# 5V_-_3_3V_regulator.net
KiCad netlist of a schematic drawn in Altium Designer
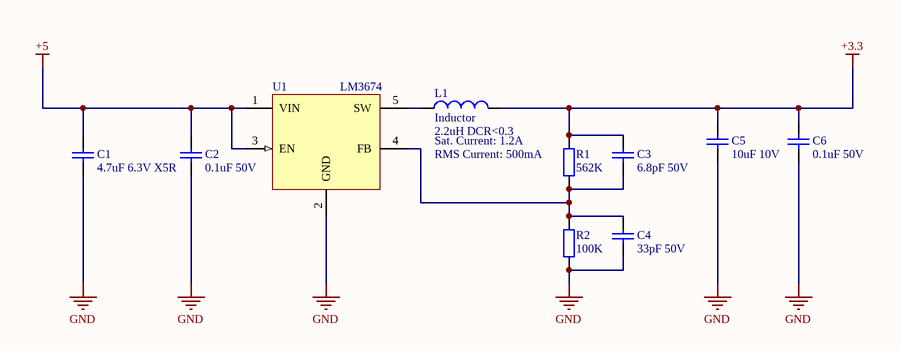
[diagram p0: 5V - 3.3V regulator.SchDoc]

(export (version "E")
  (design (tool "Eeschema 10.0.6"))
  (components
    (comp (ref "C1")
      (value "4.7uF 6.3V X5R")
      (description "Capacitor")
      (fields (field (name "Comment") "Cap"))
      (libsource (lib "Miscellaneous Devices") (part "Cap"))
    )
    (comp (ref "C2")
      (value "0.1uF 50V")
      (description "Capacitor")
      (fields (field (name "Comment") "Cap"))
      (libsource (lib "Miscellaneous Devices") (part "Cap"))
    )
    (comp (ref "C3")
      (value "6.8pF 50V")
      (description "Capacitor")
      (fields (field (name "Comment") "Cap"))
      (libsource (lib "Miscellaneous Devices") (part "Cap"))
    )
    (comp (ref "C4")
      (value "33pF 50V")
      (description "Capacitor")
      (fields (field (name "Comment") "Cap"))
      (libsource (lib "Miscellaneous Devices") (part "Cap"))
    )
    (comp (ref "C5")
      (value "10uF 10V")
      (description "Capacitor")
      (fields (field (name "Comment") "Cap"))
      (libsource (lib "Miscellaneous Devices") (part "Cap"))
    )
    (comp (ref "C6")
      (value "0.1uF 50V")
      (description "Capacitor")
      (fields (field (name "Comment") "Cap"))
      (libsource (lib "Miscellaneous Devices") (part "Cap"))
    )
    (comp (ref "L1")
      (value "Inductor")
      (footprint "B82422H1222K")
      (fields
        (field (name "ALTIUM_VALUE") "2.2uH DCR<0.3")
        (field (name "SAT. CURRENT") "1.2A")
        (field (name "RMS CURRENT") "500mA")
      )
      (libsource (lib "Miscellaneous Devices") (part "Inductor"))
    )
    (comp (ref "R1")
      (value "562K")
      (footprint "MC0603")
      (description "Resistor")
      (fields (field (name "Comment") "Res"))
      (libsource (lib "Miscellaneous Devices") (part "Res2"))
    )
    (comp (ref "R2")
      (value "100K")
      (footprint "MC0603")
      (description "Resistor")
      (fields (field (name "Comment") "Res"))
      (libsource (lib "Miscellaneous Devices") (part "Res2"))
    )
    (comp (ref "U1")
      (value "LM3674")
      (footprint "LM3674MF-ADJ")
      (description "5V STEP DOWN CONV, 600MA, POWERWISE")
      (libsource (lib "mcb") (part "LM3674"))
    )
  )
  (nets
    (net (code "1") (name "+3.3") (class "Default")
      (node (ref "C3") (pin "2") (pinfunction "2_2") (pintype "passive"))
      (node (ref "C5") (pin "2") (pinfunction "2_2") (pintype "passive"))
      (node (ref "C6") (pin "2") (pinfunction "2_2") (pintype "passive"))
      (node (ref "L1") (pin "2") (pinfunction "2_2") (pintype "passive"))
      (node (ref "R1") (pin "2") (pinfunction "2_2") (pintype "passive"))
    )
    (net (code "2") (name "+5") (class "Default")
      (node (ref "C1") (pin "2") (pinfunction "2_2") (pintype "passive"))
      (node (ref "C2") (pin "2") (pinfunction "2_2") (pintype "passive"))
      (node (ref "U1") (pin "1") (pinfunction "VIN_1") (pintype "power_in"))
      (node (ref "U1") (pin "3") (pinfunction "EN_3") (pintype "input"))
    )
    (net (code "3") (name "GND") (class "Default")
      (node (ref "C1") (pin "1") (pinfunction "1_1") (pintype "passive"))
      (node (ref "C2") (pin "1") (pinfunction "1_1") (pintype "passive"))
      (node (ref "C4") (pin "1") (pinfunction "1_1") (pintype "passive"))
      (node (ref "C5") (pin "1") (pinfunction "1_1") (pintype "passive"))
      (node (ref "C6") (pin "1") (pinfunction "1_1") (pintype "passive"))
      (node (ref "R2") (pin "1") (pinfunction "1_1") (pintype "passive"))
      (node (ref "U1") (pin "2") (pinfunction "GND_2") (pintype "power_in"))
    )
    (net (code "4") (name "Net-(U1-FB)") (class "Default")
      (node (ref "C3") (pin "1") (pinfunction "1_1") (pintype "passive"))
      (node (ref "C4") (pin "2") (pinfunction "2_2") (pintype "passive"))
      (node (ref "R1") (pin "1") (pinfunction "1_1") (pintype "passive"))
      (node (ref "R2") (pin "2") (pinfunction "2_2") (pintype "passive"))
      (node (ref "U1") (pin "4") (pinfunction "FB_4") (pintype "passive"))
    )
    (net (code "5") (name "Net-(U1-SW)") (class "Default")
      (node (ref "L1") (pin "1") (pinfunction "1_1") (pintype "passive"))
      (node (ref "U1") (pin "5") (pinfunction "SW_5") (pintype "power_in"))
    )
  )
)
